# SCH_led_project_2022-08-06.net
KiCad netlist of a schematic drawn in EasyEDA
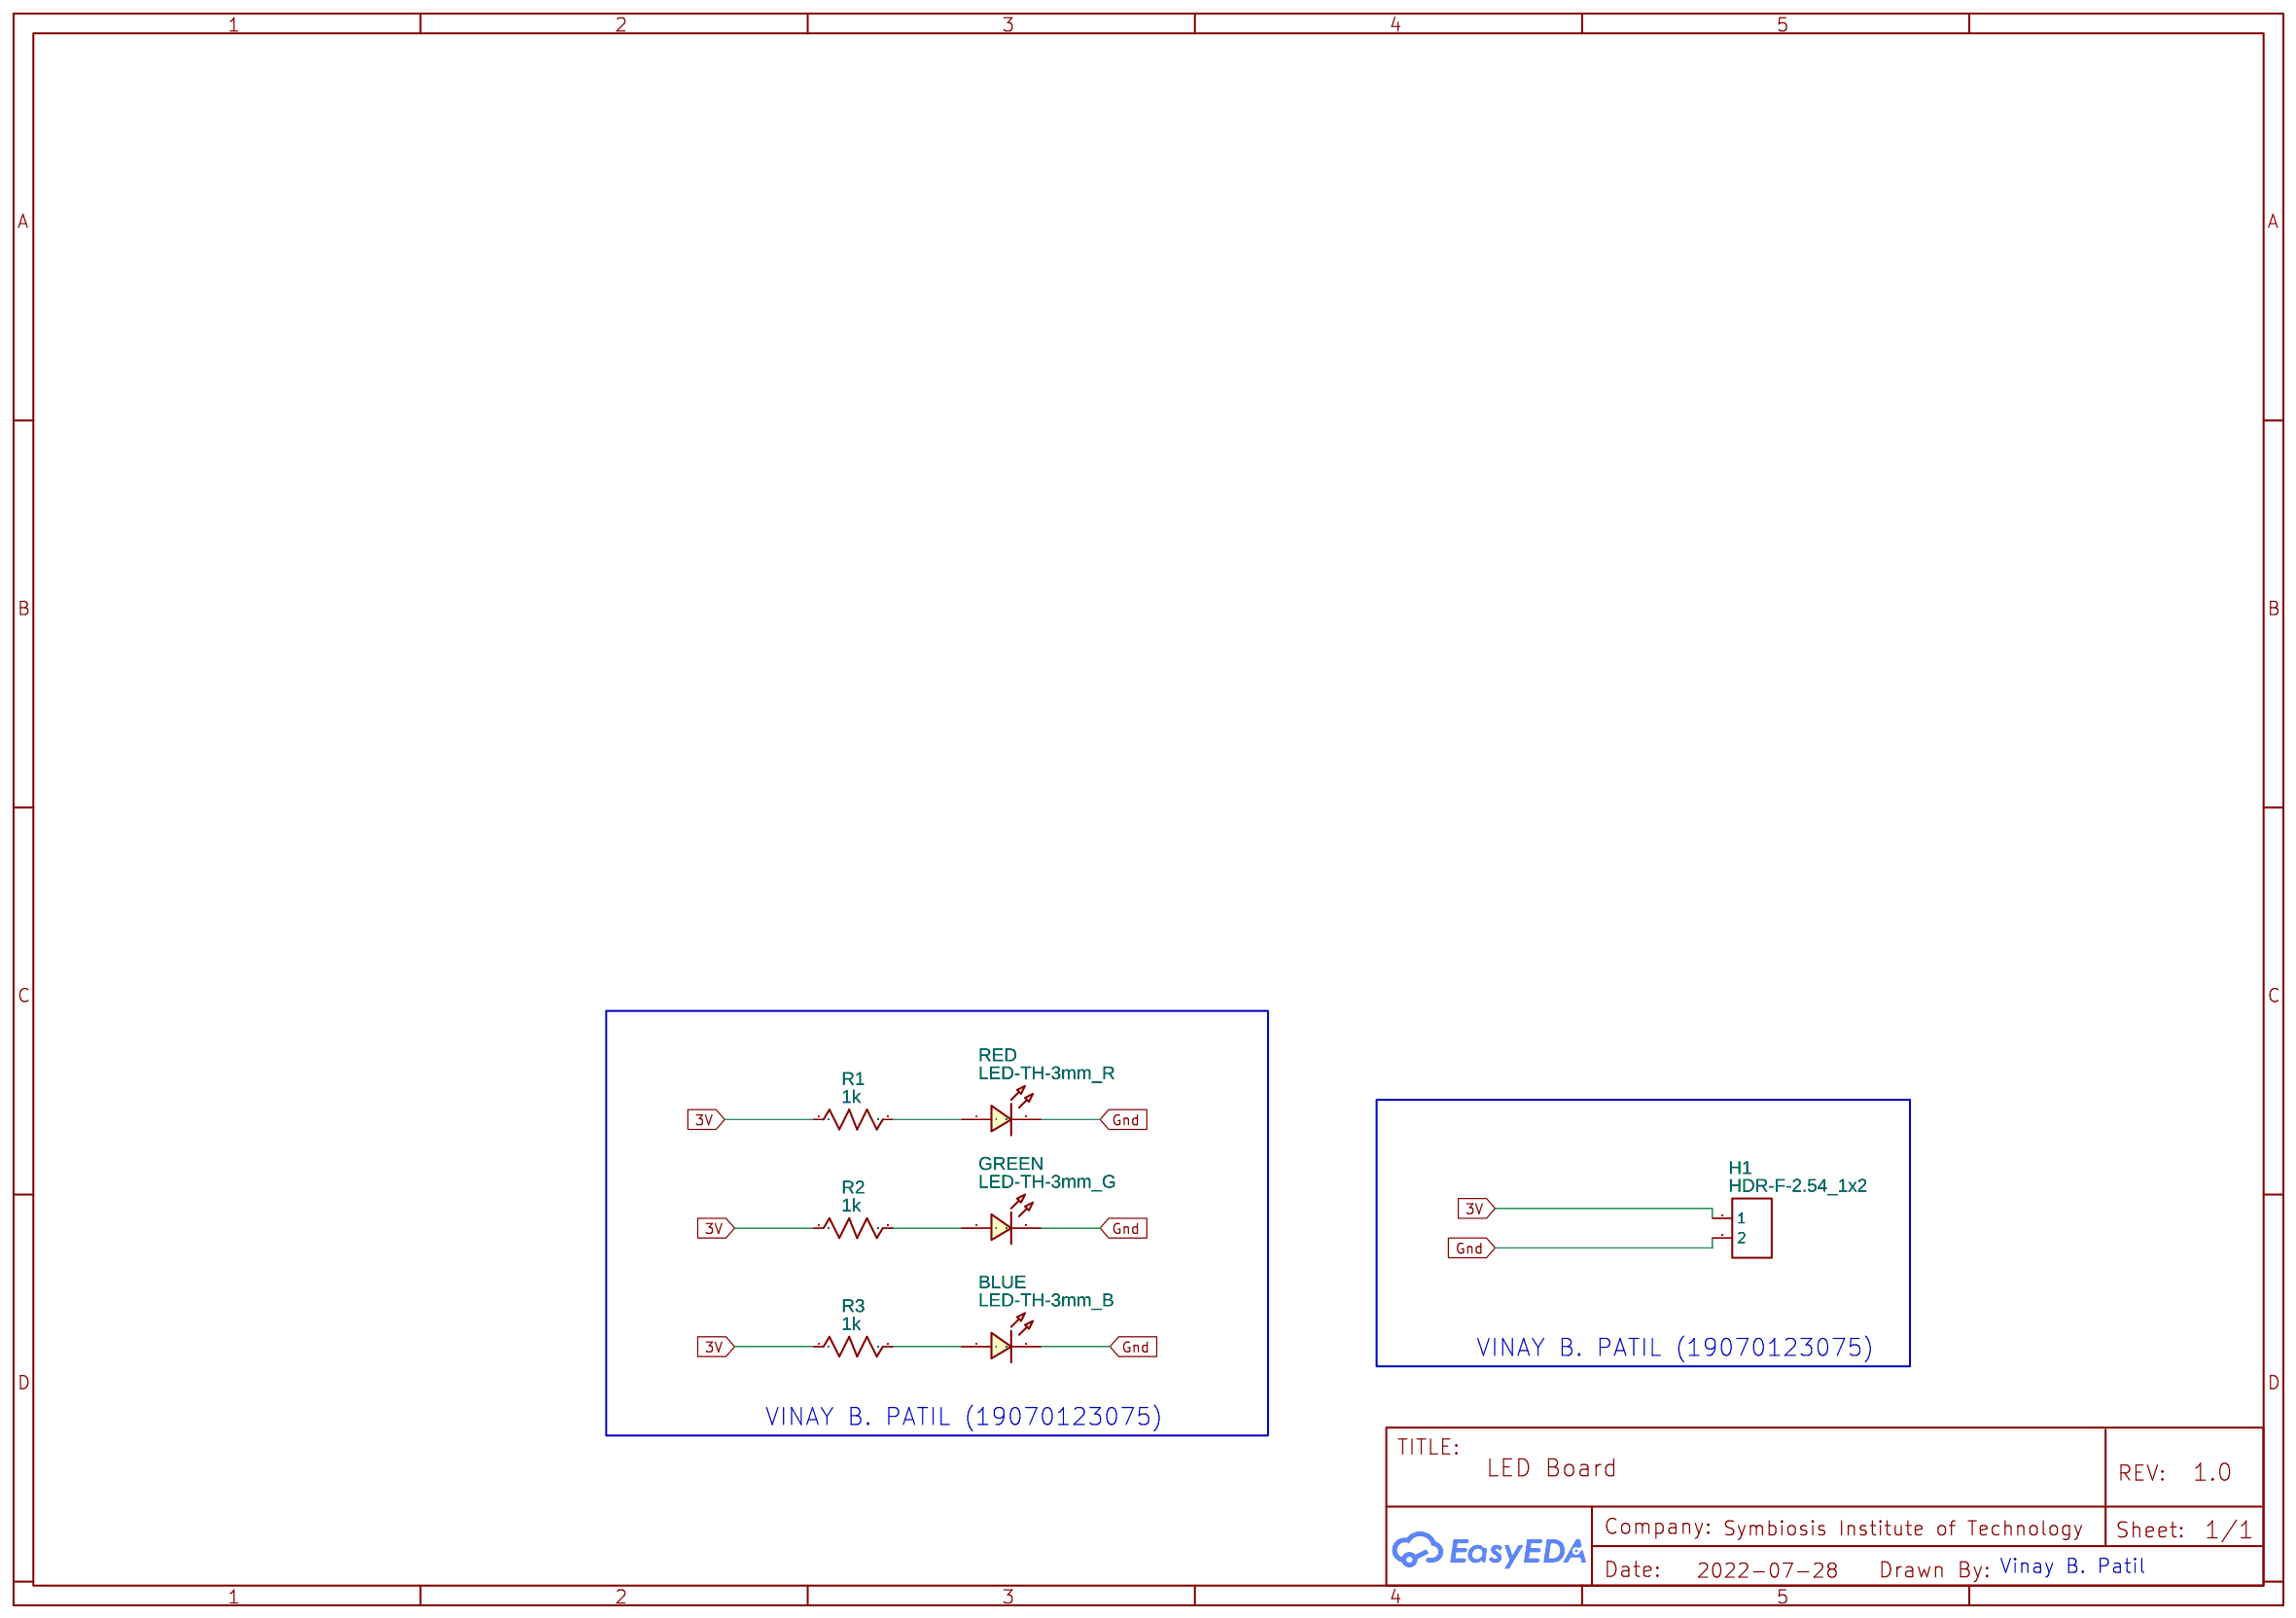
[diagram p0: schematic sheet]

(export (version "E")
  (design (tool "Eeschema 10.0.6"))
  (components
    (comp (ref "BLUE")
      (value "LED-TH-3mm_B")
      (fields
        (field (name "BOM_Manufacturer Part") "204-10SUBC/S400-A4")
        (field (name "BOM_Supplier Part") "C86881")
      )
      (libsource (lib "") (part "LED-TH-3mm_B"))
    )
    (comp (ref "GREEN")
      (value "LED-TH-3mm_G")
      (fields
        (field (name "BOM_Manufacturer Part") "204-10SYGD/S530-E3")
        (field (name "BOM_Supplier Part") "C85161")
      )
      (libsource (lib "") (part "LED-TH-3mm_G"))
    )
    (comp (ref "H1")
      (value "HDR-F-2.54_1x2")
      (fields (field (name "BOM_Supplier Part") "C49661"))
      (libsource (lib "") (part "HDR-F-2.54_1x2"))
    )
    (comp (ref "R1") (value "1k") (libsource (lib "") (part "R_AXIAL-0.3_US")))
    (comp (ref "R2") (value "1k") (libsource (lib "") (part "R_AXIAL-0.3_US")))
    (comp (ref "R3") (value "1k") (libsource (lib "") (part "R_AXIAL-0.3_US")))
    (comp (ref "RED")
      (value "LED-TH-3mm_R")
      (fields
        (field (name "BOM_Manufacturer Part") "204-10SDRD/S530-A3-L")
        (field (name "BOM_Supplier Part") "C84774")
      )
      (libsource (lib "") (part "LED-TH-3mm_R"))
    )
  )
  (nets
    (net (code "1") (name "3V") (class "Default")
      (node (ref "H1") (pin "1") (pinfunction "1_1") (pintype "input"))
      (node (ref "R1") (pin "1") (pinfunction "1_1") (pintype "unspecified"))
      (node (ref "R2") (pin "1") (pinfunction "1_1") (pintype "unspecified"))
      (node (ref "R3") (pin "1") (pinfunction "1_1") (pintype "unspecified"))
    )
    (net (code "2") (name "Gnd") (class "Default")
      (node (ref "BLUE") (pin "2") (pinfunction "2_2") (pintype "unspecified"))
      (node (ref "GREEN") (pin "2") (pinfunction "2_2") (pintype "unspecified"))
      (node (ref "H1") (pin "2") (pinfunction "2_2") (pintype "input"))
      (node (ref "RED") (pin "2") (pinfunction "2_2") (pintype "unspecified"))
    )
    (net (code "3") (name "Net-(BLUE-Pad1)") (class "Default")
      (node (ref "BLUE") (pin "1") (pinfunction "1_1") (pintype "unspecified"))
      (node (ref "R3") (pin "2") (pinfunction "2_2") (pintype "unspecified"))
    )
    (net (code "4") (name "Net-(GREEN-Pad1)") (class "Default")
      (node (ref "GREEN") (pin "1") (pinfunction "1_1") (pintype "unspecified"))
      (node (ref "R2") (pin "2") (pinfunction "2_2") (pintype "unspecified"))
    )
    (net (code "5") (name "Net-(R1-Pad2)") (class "Default")
      (node (ref "R1") (pin "2") (pinfunction "2_2") (pintype "unspecified"))
      (node (ref "RED") (pin "1") (pinfunction "1_1") (pintype "unspecified"))
    )
  )
)
